# XL_N76E003K3__MAIN.net
KiCad netlist of a schematic drawn in Altium Designer
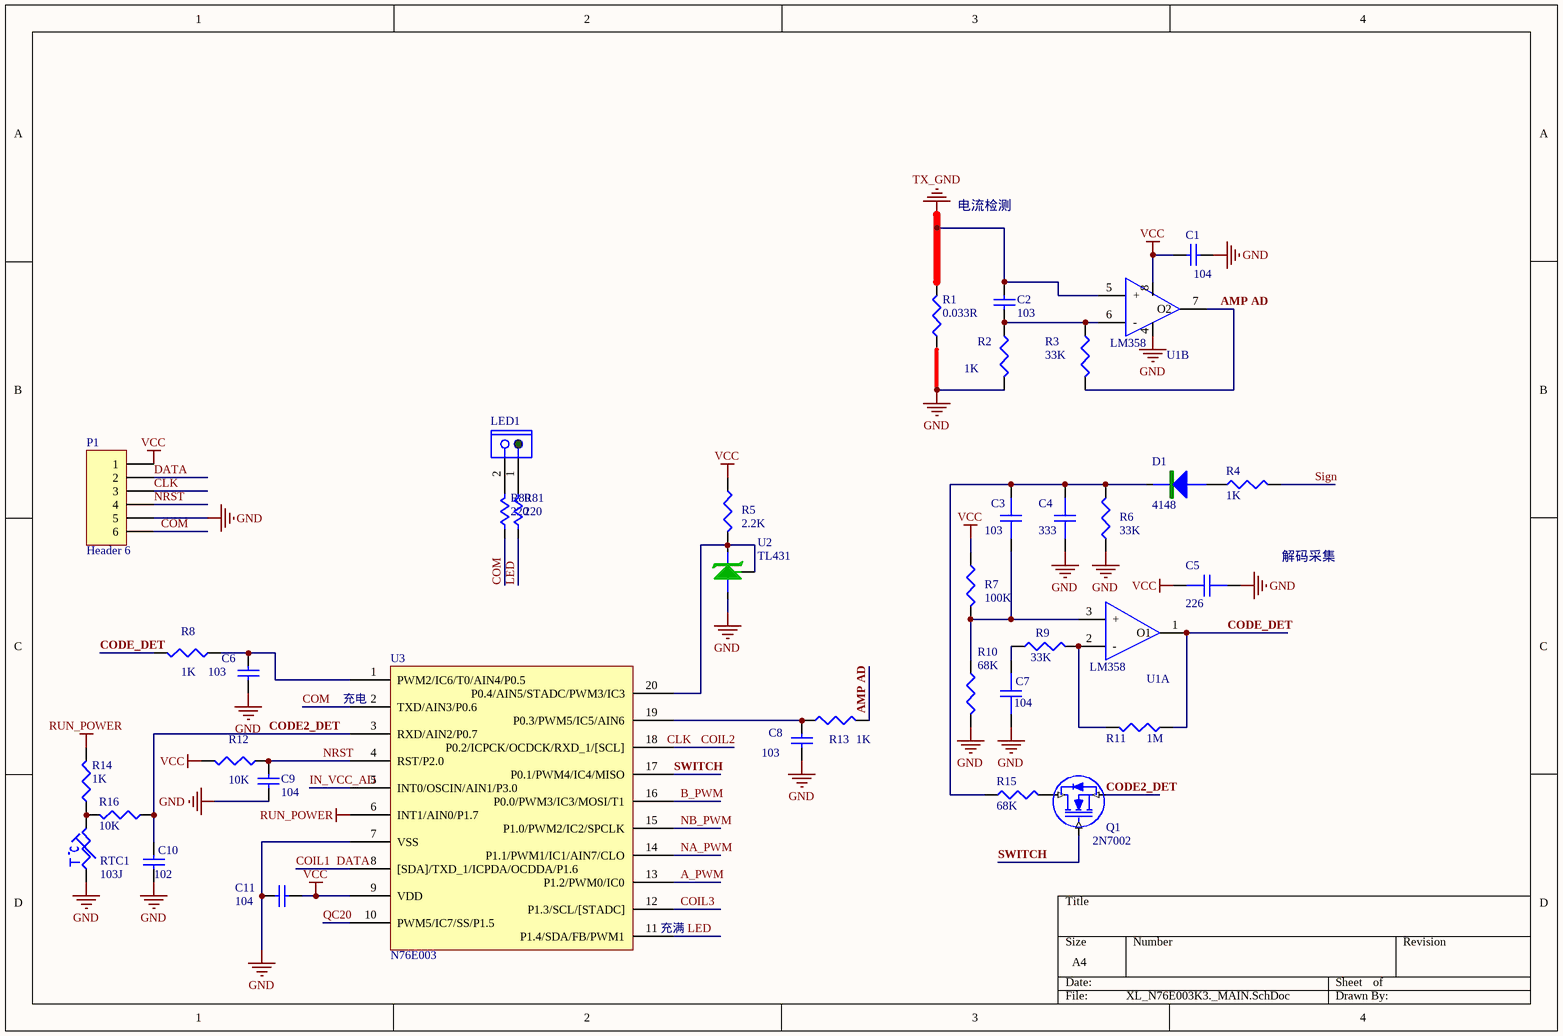
[diagram p0: XL_N76E003K3._MAIN.SchDoc]

(export (version "E")
  (design (tool "Eeschema 10.0.6"))
  (components
    (comp (ref "C1")
      (value "104")
      (footprint "C0402")
      (description "Capacitor")
      (fields (field (name "PUBLISHER") "Altium Limited"))
      (libsource (lib "*") (part "Cap"))
    )
    (comp (ref "C2")
      (value "103")
      (footprint "C0402")
      (description "Capacitor")
      (fields (field (name "PUBLISHER") "Altium Limited"))
      (libsource (lib "*") (part "Cap"))
    )
    (comp (ref "C3") (value "103") (footprint "C0402") (libsource (lib "*") (part "CH")))
    (comp (ref "C4") (value "333") (footprint "C0402") (libsource (lib "*") (part "CH")))
    (comp (ref "C5") (value "226") (footprint "C0805") (libsource (lib "*") (part "CH")))
    (comp (ref "C6")
      (value "103")
      (footprint "C0402")
      (description "Capacitor")
      (fields (field (name "PUBLISHER") "Altium Limited"))
      (libsource (lib "*") (part "Cap"))
    )
    (comp (ref "C7") (value "104") (footprint "C0402") (libsource (lib "*") (part "CH")))
    (comp (ref "C8")
      (value "103")
      (footprint "C0402")
      (description "Capacitor")
      (fields (field (name "PUBLISHER") "Altium Limited"))
      (libsource (lib "*") (part "Cap"))
    )
    (comp (ref "C9")
      (value "104")
      (footprint "C0402")
      (description "Capacitor")
      (fields (field (name "PUBLISHER") "Altium Limited"))
      (libsource (lib "*") (part "Cap"))
    )
    (comp (ref "C10")
      (value "102")
      (footprint "C0402")
      (description "Capacitor")
      (fields (field (name "PUBLISHER") "Altium Limited"))
      (libsource (lib "*") (part "Cap"))
    )
    (comp (ref "C11")
      (value "104")
      (footprint "C0402")
      (description "Capacitor")
      (fields (field (name "PUBLISHER") "Altium Limited"))
      (libsource (lib "*") (part "Cap"))
    )
    (comp (ref "D1")
      (value "4148")
      (footprint "sod323")
      (description "1N4001")
      (libsource (lib "*") (part "D0"))
    )
    (comp (ref "LED1") (value "~") (footprint "PIN2_2.54") (libsource (lib "Xin Lang") (part "CON2")))
    (comp (ref "P1")
      (value "Header 6")
      (footprint "SPIN6")
      (description "Header, 6-Pin")
      (fields (field (name "PUBLISHER") "Altium Limited"))
      (libsource (lib "Miscellaneous Connectors") (part "Header 6"))
    )
    (comp (ref "Q1") (value "2N7002") (footprint "SOT-23B") (libsource (lib "lxzschlib") (part "MOSFETN")))
    (comp (ref "R1") (value "0.033R") (footprint "R0805") (description "1K") (libsource (lib "*") (part "R")))
    (comp (ref "R2") (value "1K") (footprint "R0402") (libsource (lib "*") (part "R")))
    (comp (ref "R3") (value "33K") (footprint "R0402") (description "1K") (libsource (lib "*") (part "R")))
    (comp (ref "R4") (value "1K") (footprint "R0402") (libsource (lib "*") (part "R")))
    (comp (ref "R5") (value "2.2K") (footprint "R0402") (description "1K") (libsource (lib "*") (part "R")))
    (comp (ref "R6") (value "33K") (footprint "R0402") (description "1K") (libsource (lib "*") (part "R")))
    (comp (ref "R7") (value "100K") (footprint "R0402") (description "1K") (libsource (lib "*") (part "R")))
    (comp (ref "R8") (value "1K") (footprint "R0402") (libsource (lib "*") (part "R")))
    (comp (ref "R9") (value "33K") (footprint "R0402") (description "1K") (libsource (lib "*") (part "R")))
    (comp (ref "R10") (value "68K") (footprint "R0402") (description "1K") (libsource (lib "*") (part "R")))
    (comp (ref "R11") (value "1M") (footprint "R0402") (description "1K") (libsource (lib "*") (part "R")))
    (comp (ref "R12") (value "10K") (footprint "R0402") (libsource (lib "*") (part "R")))
    (comp (ref "R13") (value "1K") (footprint "R0402") (libsource (lib "*") (part "R")))
    (comp (ref "R14") (value "1K") (footprint "R0402") (libsource (lib "lxzschlib") (part "R")))
    (comp (ref "R15") (value "68K") (footprint "R0402") (description "1K") (libsource (lib "*") (part "R")))
    (comp (ref "R16")
      (value "10K")
      (footprint "R0402")
      (description "1K")
      (libsource (lib "lxzschlib") (part "R"))
    )
    (comp (ref "R80") (value "220") (footprint "R0402") (libsource (lib "Xin Lang") (part "Res01")))
    (comp (ref "R81") (value "220") (footprint "R0402") (libsource (lib "Xin Lang") (part "Res01")))
    (comp (ref "RTC1") (value "103J") (footprint "R0402") (libsource (lib "lxzschlib") (part "RTC")))
    (comp (ref "U1") (value "LM358") (footprint "SOP8") (libsource (lib "lxzschlib") (part "4558")))
    (comp (ref "U2")
      (value "TL431")
      (footprint "SOT-23-431")
      (description "IC")
      (libsource (lib "lxzschlib") (part "IC TL431"))
    )
    (comp (ref "U3") (value "N76E003") (footprint "SOP20") (libsource (lib "BEE802_V11") (part "103F")))
  )
  (nets
    (net (code "1") (name "/AMP AD") (class "Default")
      (node (ref "R13") (pin "2") (pintype "passive"))
      (node (ref "R3") (pin "2") (pintype "passive"))
      (node (ref "U1") (pin "7") (pinfunction "O2_7") (pintype "passive"))
    )
    (net (code "2") (name "/A_PWM") (class "Default")
      (node (ref "U3") (pin "13") (pinfunction "P1.2/PWM0/IC0_13") (pintype "passive"))
    )
    (net (code "3") (name "/B_PWM") (class "Default")
      (node (ref "U3") (pin "16") (pinfunction "P0.0/PWM3/IC3/MOSI/T1_16") (pintype "passive"))
    )
    (net (code "4") (name "/CLK") (class "Default")
      (node (ref "P1") (pin "3") (pinfunction "3_3") (pintype "passive"))
    )
    (net (code "5") (name "/CODE2_DET") (class "Default")
      (node (ref "C10") (pin "2") (pinfunction "2_2") (pintype "passive"))
      (node (ref "Q1") (pin "E") (pinfunction "S_E") (pintype "input"))
      (node (ref "R16") (pin "1") (pintype "passive"))
      (node (ref "U3") (pin "3") (pinfunction "RXD/AIN2/P0.7_3") (pintype "passive"))
    )
    (net (code "6") (name "/CODE_DET") (class "Default")
      (node (ref "R11") (pin "1") (pintype "passive"))
      (node (ref "R8") (pin "2") (pintype "passive"))
      (node (ref "U1") (pin "1") (pinfunction "O1_1") (pintype "passive"))
    )
    (net (code "7") (name "/COIL1") (class "Default")
      (node (ref "P1") (pin "2") (pinfunction "2_2") (pintype "passive"))
      (node (ref "U3") (pin "8") (pinfunction "[SDA]/TXD_1/ICPDA/OCDDA/P1.6_8") (pintype "passive"))
    )
    (net (code "8") (name "/COIL2") (class "Default")
      (node (ref "U3") (pin "18") (pinfunction "P0.2/ICPCK/OCDCK/RXD_1/[SCL]_18") (pintype "passive"))
    )
    (net (code "9") (name "/COIL3") (class "Default")
      (node (ref "U3") (pin "12") (pinfunction "P1.3/SCL/[STADC]_12") (pintype "passive"))
    )
    (net (code "10") (name "/COM") (class "Default")
      (node (ref "P1") (pin "6") (pinfunction "6_6") (pintype "passive"))
      (node (ref "R80") (pin "1") (pinfunction "1_1") (pintype "passive"))
      (node (ref "U3") (pin "2") (pinfunction "TXD/AIN3/P0.6_2") (pintype "passive"))
    )
    (net (code "11") (name "/IN_VCC_AD") (class "Default")
      (node (ref "U3") (pin "5") (pinfunction "INT0/OSCIN/AIN1/P3.0_5") (pintype "passive"))
    )
    (net (code "12") (name "/LED") (class "Default")
      (node (ref "R81") (pin "1") (pinfunction "1_1") (pintype "passive"))
      (node (ref "U3") (pin "11") (pinfunction "P1.4/SDA/FB/PWM1_11") (pintype "passive"))
    )
    (net (code "13") (name "/NA_PWM") (class "Default")
      (node (ref "U3") (pin "14") (pinfunction "P1.1/PWM1/IC1/AIN7/CLO_14") (pintype "passive"))
    )
    (net (code "14") (name "/NB_PWM") (class "Default")
      (node (ref "U3") (pin "15") (pinfunction "P1.0/PWM2/IC2/SPCLK_15") (pintype "passive"))
    )
    (net (code "15") (name "/NRST") (class "Default")
      (node (ref "C9") (pin "1") (pinfunction "1_1") (pintype "passive"))
      (node (ref "P1") (pin "4") (pinfunction "4_4") (pintype "passive"))
      (node (ref "R12") (pin "1") (pintype "passive"))
      (node (ref "U3") (pin "4") (pinfunction "RST/P2.0_4") (pintype "passive"))
    )
    (net (code "16") (name "/QC20") (class "Default")
      (node (ref "U3") (pin "10") (pinfunction "PWM5/IC7/SS/P1.5_10") (pintype "passive"))
    )
    (net (code "17") (name "/SWITCH") (class "Default")
      (node (ref "Q1") (pin "B") (pinfunction "G_B") (pintype "input"))
      (node (ref "U3") (pin "17") (pinfunction "P0.1/PWM4/IC4/MISO_17") (pintype "passive"))
    )
    (net (code "18") (name "/Sign") (class "Default") (node (ref "R4") (pin "2") (pintype "passive")))
    (net (code "19") (name "GND") (class "Default")
      (node (ref "C1") (pin "1") (pinfunction "1_1") (pintype "passive"))
      (node (ref "C10") (pin "1") (pinfunction "1_1") (pintype "passive"))
      (node (ref "C11") (pin "1") (pinfunction "1_1") (pintype "passive"))
      (node (ref "C4") (pin "1") (pintype "passive"))
      (node (ref "C5") (pin "1") (pintype "passive"))
      (node (ref "C6") (pin "1") (pinfunction "1_1") (pintype "passive"))
      (node (ref "C7") (pin "1") (pintype "passive"))
      (node (ref "C8") (pin "2") (pinfunction "2_2") (pintype "passive"))
      (node (ref "C9") (pin "2") (pinfunction "2_2") (pintype "passive"))
      (node (ref "P1") (pin "5") (pinfunction "5_5") (pintype "passive"))
      (node (ref "R1") (pin "1") (pintype "passive"))
      (node (ref "R10") (pin "2") (pintype "passive"))
      (node (ref "R2") (pin "2") (pintype "passive"))
      (node (ref "R6") (pin "1") (pintype "passive"))
      (node (ref "RTC1") (pin "1") (pintype "passive"))
      (node (ref "U1") (pin "4") (pintype "passive"))
      (node (ref "U2") (pin "1") (pintype "passive"))
      (node (ref "U3") (pin "7") (pinfunction "VSS_7") (pintype "passive"))
    )
    (net (code "20") (name "Net-(C3-Pad1)") (class "Default")
      (node (ref "C3") (pin "1") (pintype "passive"))
      (node (ref "C4") (pin "2") (pintype "passive"))
      (node (ref "D1") (pin "2") (pintype "passive"))
      (node (ref "R15") (pin "1") (pintype "passive"))
      (node (ref "R6") (pin "2") (pintype "passive"))
    )
    (net (code "21") (name "Net-(C7-Pad2)") (class "Default")
      (node (ref "C7") (pin "2") (pintype "passive"))
      (node (ref "R9") (pin "1") (pintype "passive"))
    )
    (net (code "22") (name "Net-(D1-Pad1)") (class "Default")
      (node (ref "D1") (pin "1") (pintype "passive"))
      (node (ref "R4") (pin "1") (pintype "passive"))
    )
    (net (code "23") (name "Net-(LED1-Pad1)") (class "Default")
      (node (ref "LED1") (pin "1") (pintype "passive"))
      (node (ref "R81") (pin "2") (pinfunction "2_2") (pintype "passive"))
    )
    (net (code "24") (name "Net-(LED1-Pad2)") (class "Default")
      (node (ref "LED1") (pin "2") (pintype "passive"))
      (node (ref "R80") (pin "2") (pinfunction "2_2") (pintype "passive"))
    )
    (net (code "25") (name "Net-(Q1-D)") (class "Default")
      (node (ref "Q1") (pin "C") (pinfunction "D_C") (pintype "input"))
      (node (ref "R15") (pin "2") (pintype "passive"))
    )
    (net (code "26") (name "Net-(R14-Pad1)") (class "Default")
      (node (ref "R14") (pin "1") (pintype "passive"))
      (node (ref "R16") (pin "2") (pintype "passive"))
      (node (ref "RTC1") (pin "2") (pintype "passive"))
    )
    (net (code "27") (name "Net-(U1A-+)") (class "Default")
      (node (ref "C3") (pin "2") (pintype "passive"))
      (node (ref "R10") (pin "1") (pintype "passive"))
      (node (ref "R7") (pin "2") (pintype "passive"))
      (node (ref "U1") (pin "3") (pinfunction "+_3") (pintype "passive"))
    )
    (net (code "28") (name "Net-(U1A--)") (class "Default")
      (node (ref "R11") (pin "2") (pintype "passive"))
      (node (ref "R9") (pin "2") (pintype "passive"))
      (node (ref "U1") (pin "2") (pinfunction "-_2") (pintype "passive"))
    )
    (net (code "29") (name "Net-(U1B--)") (class "Default")
      (node (ref "C2") (pin "2") (pinfunction "2_2") (pintype "passive"))
      (node (ref "R2") (pin "1") (pintype "passive"))
      (node (ref "R3") (pin "1") (pintype "passive"))
      (node (ref "U1") (pin "6") (pinfunction "-_6") (pintype "passive"))
    )
    (net (code "30") (name "Net-(U3-P0.3{slash}PWM5{slash}IC5{slash}AIN6)") (class "Default")
      (node (ref "C8") (pin "1") (pinfunction "1_1") (pintype "passive"))
      (node (ref "R13") (pin "1") (pintype "passive"))
      (node (ref "U3") (pin "19") (pinfunction "P0.3/PWM5/IC5/AIN6_19") (pintype "passive"))
    )
    (net (code "31") (name "Net-(U3-P0.4{slash}AIN5{slash}STADC{slash}PWM3{slash}IC3)") (class "Default")
      (node (ref "R5") (pin "2") (pintype "passive"))
      (node (ref "U2") (pin "2") (pintype "passive"))
      (node (ref "U2") (pin "3") (pintype "passive"))
      (node (ref "U3") (pin "20") (pinfunction "P0.4/AIN5/STADC/PWM3/IC3_20") (pintype "passive"))
    )
    (net (code "32") (name "Net-(U3-PWM2{slash}IC6{slash}T0{slash}AIN4{slash}P0.5)") (class "Default")
      (node (ref "C6") (pin "2") (pinfunction "2_2") (pintype "passive"))
      (node (ref "R8") (pin "1") (pintype "passive"))
      (node (ref "U3") (pin "1") (pinfunction "PWM2/IC6/T0/AIN4/P0.5_1") (pintype "passive"))
    )
    (net (code "33") (name "RUN_POWER") (class "Default")
      (node (ref "R14") (pin "2") (pintype "passive"))
      (node (ref "U3") (pin "6") (pinfunction "INT1/AIN0/P1.7_6") (pintype "passive"))
    )
    (net (code "34") (name "TX_GND") (class "Default")
      (node (ref "C2") (pin "1") (pinfunction "1_1") (pintype "passive"))
      (node (ref "R1") (pin "2") (pintype "passive"))
      (node (ref "U1") (pin "5") (pinfunction "+_5") (pintype "passive"))
    )
    (net (code "35") (name "VCC") (class "Default")
      (node (ref "C1") (pin "2") (pinfunction "2_2") (pintype "passive"))
      (node (ref "C11") (pin "2") (pinfunction "2_2") (pintype "passive"))
      (node (ref "C5") (pin "2") (pintype "passive"))
      (node (ref "P1") (pin "1") (pinfunction "1_1") (pintype "passive"))
      (node (ref "R12") (pin "2") (pintype "passive"))
      (node (ref "R5") (pin "1") (pintype "passive"))
      (node (ref "R7") (pin "1") (pintype "passive"))
      (node (ref "U1") (pin "8") (pintype "passive"))
      (node (ref "U3") (pin "9") (pinfunction "VDD_9") (pintype "passive"))
    )
  )
)
